# Controller.net
KiCad netlist of a schematic drawn in Altium Designer
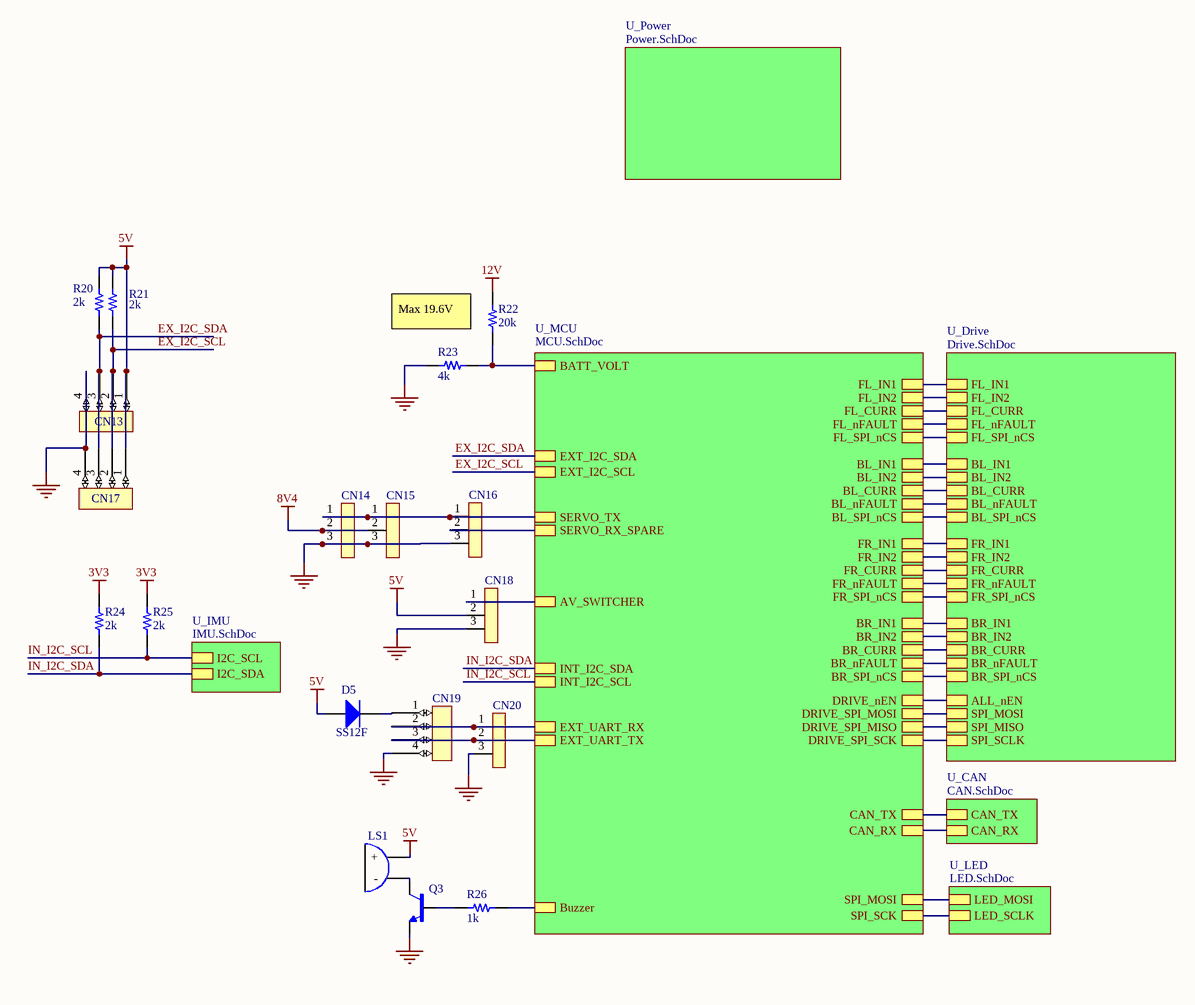
[diagram p0: Controller.SchDoc]

(export (version "E")
  (design (tool "Eeschema 10.0.6"))
  (components
    (comp (ref "CN13")
      (value "JST_GH-4P")
      (footprint "JST_GH-4P")
      (libsource (lib "Parts") (part "JST_GH-4P"))
    )
    (comp (ref "CN14") (value "3P-2.5mm") (footprint "2.5mm-3P") (libsource (lib "Parts") (part "3P-2.5mm")))
    (comp (ref "CN15") (value "3P-2.5mm") (footprint "2.5mm-3P") (libsource (lib "Parts") (part "3P-2.5mm")))
    (comp (ref "CN16") (value "3P-2.5mm") (footprint "2.5mm-3P") (libsource (lib "Parts") (part "3P-2.5mm")))
    (comp (ref "CN17")
      (value "JST_GH-4P")
      (footprint "JST_GH-4P")
      (libsource (lib "Parts") (part "JST_GH-4P"))
    )
    (comp (ref "CN18") (value "3P-2.5mm") (footprint "2.5mm-3P") (libsource (lib "Parts") (part "3P-2.5mm")))
    (comp (ref "CN19") (value "JST_GH-4P") (footprint "JST_GH-4P") (libsource (lib "") (part "JST_GH-4P_1")))
    (comp (ref "CN20") (value "3P-2.5mm") (footprint "2.5mm-3P") (libsource (lib "Parts") (part "3P-2.5mm")))
    (comp (ref "D5") (value "SS12F") (footprint "SMAF_DIODE") (libsource (lib "Parts") (part "SS12F")))
    (comp (ref "LS1") (value "Buzzer") (footprint "12-dia-buzzer") (libsource (lib "Parts") (part "Buzzer")))
    (comp (ref "Q3")
      (value "S8050")
      (footprint "SOT23-FET")
      (fields
        (field (name "MF") "MICROSS/On Semiconductor")
        (field (name "DIGI-KEY_PART_NUMBER") "1086-15156-ND")
        (field (name "MP") "2N2222")
      )
      (libsource (lib "Parts") (part "S8050"))
    )
    (comp (ref "R20")
      (value "2k")
      (footprint "2010_SMD_Resistor")
      (libsource (lib "Parts") (part "Resistor"))
    )
    (comp (ref "R21")
      (value "2k")
      (footprint "2010_SMD_Resistor")
      (libsource (lib "Parts") (part "Resistor"))
    )
    (comp (ref "R22")
      (value "20k")
      (footprint "0805 - duplicate")
      (libsource (lib "Parts") (part "Resistor"))
    )
    (comp (ref "R23") (value "4k") (footprint "0805 - duplicate") (libsource (lib "Parts") (part "Resistor")))
    (comp (ref "R24") (value "2k") (footprint "0805 - duplicate") (libsource (lib "Parts") (part "Resistor")))
    (comp (ref "R25") (value "2k") (footprint "0805 - duplicate") (libsource (lib "Parts") (part "Resistor")))
    (comp (ref "R26") (value "1k") (footprint "0805 - duplicate") (libsource (lib "Parts") (part "Resistor")))
  )
  (nets
    (net (code "2") (name "/AV_SWITCHER") (class "Default") (node (ref "CN18") (pin "1") (pintype "passive")))
    (net (code "3") (name "/BATT_VOLT") (class "Default")
      (node (ref "R22") (pin "1") (pinfunction "1_1") (pintype "passive"))
      (node (ref "R23") (pin "1") (pinfunction "1_1") (pintype "passive"))
    )
    (net (code "14") (name "/Buzzer") (class "Default")
      (node (ref "R26") (pin "2") (pinfunction "2_2") (pintype "passive"))
    )
    (net (code "20") (name "/EXT_UART_RX") (class "Default")
      (node (ref "CN19") (pin "2") (pintype "bidirectional"))
      (node (ref "CN20") (pin "1") (pintype "passive"))
    )
    (net (code "21") (name "/EXT_UART_TX") (class "Default")
      (node (ref "CN19") (pin "3") (pintype "bidirectional"))
      (node (ref "CN20") (pin "2") (pintype "passive"))
    )
    (net (code "22") (name "/EX_I2C_SCL") (class "Default")
      (node (ref "CN13") (pin "2") (pintype "bidirectional"))
      (node (ref "CN17") (pin "2") (pintype "bidirectional"))
      (node (ref "R21") (pin "1") (pinfunction "1_1") (pintype "passive"))
    )
    (net (code "23") (name "/EX_I2C_SDA") (class "Default")
      (node (ref "CN13") (pin "3") (pintype "bidirectional"))
      (node (ref "CN17") (pin "3") (pintype "bidirectional"))
      (node (ref "R20") (pin "1") (pinfunction "1_1") (pintype "passive"))
    )
    (net (code "34") (name "/IN_I2C_SCL") (class "Default")
      (node (ref "R25") (pin "1") (pinfunction "1_1") (pintype "passive"))
    )
    (net (code "35") (name "/IN_I2C_SDA") (class "Default")
      (node (ref "R24") (pin "1") (pinfunction "1_1") (pintype "passive"))
    )
    (net (code "38") (name "/SERVO_RX_SPARE") (class "Default")
      (node (ref "CN16") (pin "2") (pintype "passive"))
    )
    (net (code "39") (name "/SERVO_TX") (class "Default")
      (node (ref "CN14") (pin "1") (pintype "passive"))
      (node (ref "CN15") (pin "1") (pintype "passive"))
      (node (ref "CN16") (pin "1") (pintype "passive"))
    )
    (net (code "40") (name "3V3") (class "Default")
      (node (ref "R24") (pin "2") (pinfunction "2_2") (pintype "passive"))
      (node (ref "R25") (pin "2") (pinfunction "2_2") (pintype "passive"))
    )
    (net (code "41") (name "5V") (class "Default")
      (node (ref "CN13") (pin "1") (pintype "bidirectional"))
      (node (ref "CN17") (pin "1") (pintype "bidirectional"))
      (node (ref "CN18") (pin "2") (pintype "passive"))
      (node (ref "D5") (pin "1") (pinfunction "A_1") (pintype "passive"))
      (node (ref "LS1") (pin "A") (pinfunction "+_A") (pintype "passive"))
      (node (ref "R20") (pin "2") (pinfunction "2_2") (pintype "passive"))
      (node (ref "R21") (pin "2") (pinfunction "2_2") (pintype "passive"))
    )
    (net (code "42") (name "8V4") (class "Default")
      (node (ref "CN14") (pin "2") (pintype "passive"))
      (node (ref "CN15") (pin "2") (pintype "passive"))
    )
    (net (code "43") (name "12V") (class "Default")
      (node (ref "R22") (pin "2") (pinfunction "2_2") (pintype "passive"))
    )
    (net (code "44") (name "GND") (class "Default")
      (node (ref "CN13") (pin "4") (pintype "bidirectional"))
      (node (ref "CN14") (pin "3") (pintype "passive"))
      (node (ref "CN15") (pin "3") (pintype "passive"))
      (node (ref "CN16") (pin "3") (pintype "passive"))
      (node (ref "CN17") (pin "4") (pintype "bidirectional"))
      (node (ref "CN18") (pin "3") (pintype "passive"))
      (node (ref "CN19") (pin "4") (pintype "bidirectional"))
      (node (ref "CN20") (pin "3") (pintype "passive"))
      (node (ref "Q3") (pin "2") (pinfunction "E_2") (pintype "passive"))
      (node (ref "R23") (pin "2") (pinfunction "2_2") (pintype "passive"))
    )
    (net (code "45") (name "Net-(D5-K)") (class "Default")
      (node (ref "CN19") (pin "1") (pintype "bidirectional"))
      (node (ref "D5") (pin "2") (pinfunction "K_2") (pintype "passive"))
    )
    (net (code "46") (name "Net-(LS1--)") (class "Default")
      (node (ref "LS1") (pin "K") (pinfunction "-_K") (pintype "passive"))
      (node (ref "Q3") (pin "3") (pinfunction "C_3") (pintype "passive"))
    )
    (net (code "47") (name "Net-(Q3-B)") (class "Default")
      (node (ref "Q3") (pin "1") (pinfunction "B_1") (pintype "passive"))
      (node (ref "R26") (pin "1") (pinfunction "1_1") (pintype "passive"))
    )
  )
)
